# 18-de-77.net
KiCad netlist of a schematic drawn in EAGLE
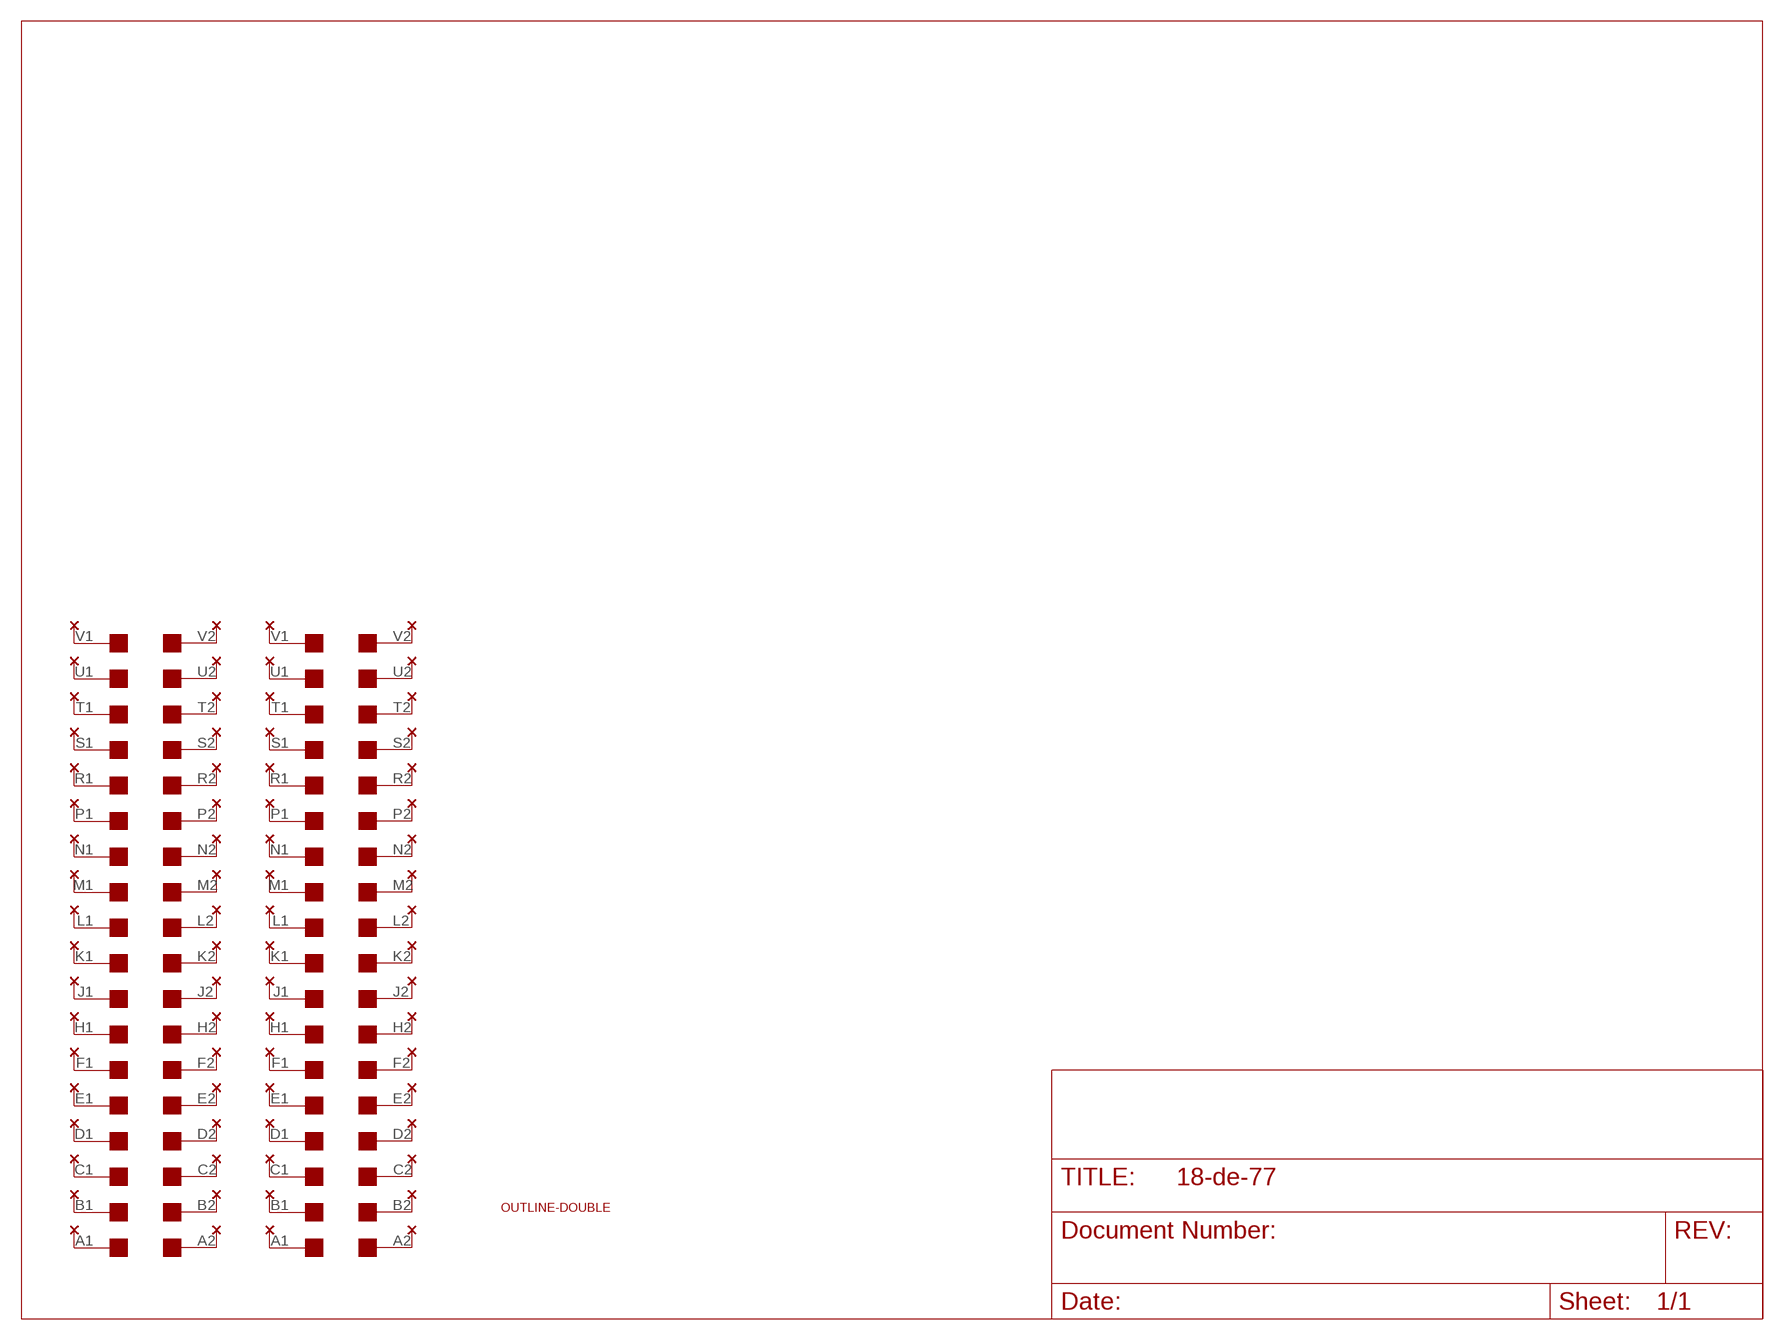
[diagram p0: schematic, sheet 1]

(export (version "E")
  (design (tool "Eeschema 10.0.6"))
  (components
    (comp (ref "U$1")
      (value "SINGLE")
      (footprint "eagle-import:EDGE-CON2")
      (libsource (lib "eagle-import") (part "SINGLE"))
    )
    (comp (ref "U$2")
      (value "THRU-HOLE2A")
      (footprint "eagle-import:THRU-HOLEA")
      (libsource (lib "eagle-import") (part "THRU-HOLE2A"))
    )
    (comp (ref "U$3")
      (value "THRU-HOLE2A")
      (footprint "eagle-import:THRU-HOLEA")
      (libsource (lib "eagle-import") (part "THRU-HOLE2A"))
    )
    (comp (ref "U$4")
      (value "OUTLINE-DOUBLE")
      (footprint "eagle-import:DOUBLE")
      (libsource (lib "eagle-import") (part "OUTLINE-DOUBLE"))
    )
    (comp (ref "U$6")
      (value "SINGLE")
      (footprint "eagle-import:EDGE-CON2")
      (libsource (lib "eagle-import") (part "SINGLE"))
    )
  )
  (nets
    (net (code "1") (name "Net-(U$1A-1)") (class "Default")
      (node (ref "U$1") (pin "A1") (pinfunction "1_A1") (pintype "bidirectional"))
      (node (ref "U$2") (pin "A1") (pinfunction "P$1_A1") (pintype "passive"))
    )
    (net (code "2") (name "Net-(U$1AA-1)") (class "Default")
      (node (ref "U$1") (pin "R1") (pinfunction "1_R1") (pintype "bidirectional"))
      (node (ref "U$2") (pin "R1") (pinfunction "P$1_R1") (pintype "passive"))
    )
    (net (code "3") (name "Net-(U$1AB-1)") (class "Default")
      (node (ref "U$1") (pin "R2") (pinfunction "1_R2") (pintype "bidirectional"))
      (node (ref "U$2") (pin "R2") (pinfunction "P$1_R2") (pintype "passive"))
    )
    (net (code "4") (name "Net-(U$1AC-1)") (class "Default")
      (node (ref "U$1") (pin "S1") (pinfunction "1_S1") (pintype "bidirectional"))
      (node (ref "U$2") (pin "S1") (pinfunction "P$1_S1") (pintype "passive"))
    )
    (net (code "5") (name "Net-(U$1AD-1)") (class "Default")
      (node (ref "U$1") (pin "S2") (pinfunction "1_S2") (pintype "bidirectional"))
      (node (ref "U$2") (pin "S2") (pinfunction "P$1_S2") (pintype "passive"))
    )
    (net (code "6") (name "Net-(U$1AE-1)") (class "Default")
      (node (ref "U$1") (pin "T1") (pinfunction "1_T1") (pintype "bidirectional"))
      (node (ref "U$2") (pin "T1") (pinfunction "P$1_T1") (pintype "passive"))
    )
    (net (code "7") (name "Net-(U$1AF-1)") (class "Default")
      (node (ref "U$1") (pin "T2") (pinfunction "1_T2") (pintype "bidirectional"))
      (node (ref "U$2") (pin "T2") (pinfunction "P$1_T2") (pintype "passive"))
    )
    (net (code "8") (name "Net-(U$1AG-1)") (class "Default")
      (node (ref "U$1") (pin "U1") (pinfunction "1_U1") (pintype "bidirectional"))
      (node (ref "U$2") (pin "U1") (pinfunction "P$1_U1") (pintype "passive"))
    )
    (net (code "9") (name "Net-(U$1AH-1)") (class "Default")
      (node (ref "U$1") (pin "U2") (pinfunction "1_U2") (pintype "bidirectional"))
      (node (ref "U$2") (pin "U2") (pinfunction "P$1_U2") (pintype "passive"))
    )
    (net (code "10") (name "Net-(U$1AI-1)") (class "Default")
      (node (ref "U$1") (pin "V1") (pinfunction "1_V1") (pintype "bidirectional"))
      (node (ref "U$2") (pin "V1") (pinfunction "P$1_V1") (pintype "passive"))
    )
    (net (code "11") (name "Net-(U$1AJ-1)") (class "Default")
      (node (ref "U$1") (pin "V2") (pinfunction "1_V2") (pintype "bidirectional"))
      (node (ref "U$2") (pin "V2") (pinfunction "P$1_V2") (pintype "passive"))
    )
    (net (code "12") (name "Net-(U$1B-1)") (class "Default")
      (node (ref "U$1") (pin "A2") (pinfunction "1_A2") (pintype "bidirectional"))
      (node (ref "U$2") (pin "A2") (pinfunction "P$1_A2") (pintype "passive"))
    )
    (net (code "13") (name "Net-(U$1C-1)") (class "Default")
      (node (ref "U$1") (pin "B1") (pinfunction "1_B1") (pintype "bidirectional"))
      (node (ref "U$2") (pin "B1") (pinfunction "P$1_B1") (pintype "passive"))
    )
    (net (code "14") (name "Net-(U$1D-1)") (class "Default")
      (node (ref "U$1") (pin "B2") (pinfunction "1_B2") (pintype "bidirectional"))
      (node (ref "U$2") (pin "B2") (pinfunction "P$1_B2") (pintype "passive"))
    )
    (net (code "15") (name "Net-(U$1E-1)") (class "Default")
      (node (ref "U$1") (pin "C1") (pinfunction "1_C1") (pintype "bidirectional"))
      (node (ref "U$2") (pin "C1") (pinfunction "P$1_C1") (pintype "passive"))
    )
    (net (code "16") (name "Net-(U$1F-1)") (class "Default")
      (node (ref "U$1") (pin "C2") (pinfunction "1_C2") (pintype "bidirectional"))
      (node (ref "U$2") (pin "C2") (pinfunction "P$1_C2") (pintype "passive"))
    )
    (net (code "17") (name "Net-(U$1G-1)") (class "Default")
      (node (ref "U$1") (pin "D1") (pinfunction "1_D1") (pintype "bidirectional"))
      (node (ref "U$2") (pin "D1") (pinfunction "P$1_D1") (pintype "passive"))
    )
    (net (code "18") (name "Net-(U$1H-1)") (class "Default")
      (node (ref "U$1") (pin "D2") (pinfunction "1_D2") (pintype "bidirectional"))
      (node (ref "U$2") (pin "D2") (pinfunction "P$1_D2") (pintype "passive"))
    )
    (net (code "19") (name "Net-(U$1I-1)") (class "Default")
      (node (ref "U$1") (pin "E1") (pinfunction "1_E1") (pintype "bidirectional"))
      (node (ref "U$2") (pin "E1") (pinfunction "P$1_E1") (pintype "passive"))
    )
    (net (code "20") (name "Net-(U$1J-1)") (class "Default")
      (node (ref "U$1") (pin "E2") (pinfunction "1_E2") (pintype "bidirectional"))
      (node (ref "U$2") (pin "E2") (pinfunction "P$1_E2") (pintype "passive"))
    )
    (net (code "21") (name "Net-(U$1K-1)") (class "Default")
      (node (ref "U$1") (pin "F1") (pinfunction "1_F1") (pintype "bidirectional"))
      (node (ref "U$2") (pin "F1") (pinfunction "P$1_F1") (pintype "passive"))
    )
    (net (code "22") (name "Net-(U$1L-1)") (class "Default")
      (node (ref "U$1") (pin "F2") (pinfunction "1_F2") (pintype "bidirectional"))
      (node (ref "U$2") (pin "F2") (pinfunction "P$1_F2") (pintype "passive"))
    )
    (net (code "23") (name "Net-(U$1M-1)") (class "Default")
      (node (ref "U$1") (pin "H1") (pinfunction "1_H1") (pintype "bidirectional"))
      (node (ref "U$2") (pin "H1") (pinfunction "P$1_H1") (pintype "passive"))
    )
    (net (code "24") (name "Net-(U$1N-1)") (class "Default")
      (node (ref "U$1") (pin "H2") (pinfunction "1_H2") (pintype "bidirectional"))
      (node (ref "U$2") (pin "H2") (pinfunction "P$1_H2") (pintype "passive"))
    )
    (net (code "25") (name "Net-(U$1O-1)") (class "Default")
      (node (ref "U$1") (pin "J1") (pinfunction "1_J1") (pintype "bidirectional"))
      (node (ref "U$2") (pin "J1") (pinfunction "P$1_J1") (pintype "passive"))
    )
    (net (code "26") (name "Net-(U$1P-1)") (class "Default")
      (node (ref "U$1") (pin "J2") (pinfunction "1_J2") (pintype "bidirectional"))
      (node (ref "U$2") (pin "J2") (pinfunction "P$1_J2") (pintype "passive"))
    )
    (net (code "27") (name "Net-(U$1Q-1)") (class "Default")
      (node (ref "U$1") (pin "K1") (pinfunction "1_K1") (pintype "bidirectional"))
      (node (ref "U$2") (pin "K1") (pinfunction "P$1_K1") (pintype "passive"))
    )
    (net (code "28") (name "Net-(U$1R-1)") (class "Default")
      (node (ref "U$1") (pin "K2") (pinfunction "1_K2") (pintype "bidirectional"))
      (node (ref "U$2") (pin "K2") (pinfunction "P$1_K2") (pintype "passive"))
    )
    (net (code "29") (name "Net-(U$1S-1)") (class "Default")
      (node (ref "U$1") (pin "L1") (pinfunction "1_L1") (pintype "bidirectional"))
      (node (ref "U$2") (pin "L1") (pinfunction "P$1_L1") (pintype "passive"))
    )
    (net (code "30") (name "Net-(U$1T-1)") (class "Default")
      (node (ref "U$1") (pin "L2") (pinfunction "1_L2") (pintype "bidirectional"))
      (node (ref "U$2") (pin "L2") (pinfunction "P$1_L2") (pintype "passive"))
    )
    (net (code "31") (name "Net-(U$1U-1)") (class "Default")
      (node (ref "U$1") (pin "M1") (pinfunction "1_M1") (pintype "bidirectional"))
      (node (ref "U$2") (pin "M1") (pinfunction "P$1_M1") (pintype "passive"))
    )
    (net (code "32") (name "Net-(U$1V-1)") (class "Default")
      (node (ref "U$1") (pin "M2") (pinfunction "1_M2") (pintype "bidirectional"))
      (node (ref "U$2") (pin "M2") (pinfunction "P$1_M2") (pintype "passive"))
    )
    (net (code "33") (name "Net-(U$1W-1)") (class "Default")
      (node (ref "U$1") (pin "N1") (pinfunction "1_N1") (pintype "bidirectional"))
      (node (ref "U$2") (pin "N1") (pinfunction "P$1_N1") (pintype "passive"))
    )
    (net (code "34") (name "Net-(U$1X-1)") (class "Default")
      (node (ref "U$1") (pin "N2") (pinfunction "1_N2") (pintype "bidirectional"))
      (node (ref "U$2") (pin "N2") (pinfunction "P$1_N2") (pintype "passive"))
    )
    (net (code "35") (name "Net-(U$1Y-1)") (class "Default")
      (node (ref "U$1") (pin "P1") (pinfunction "1_P1") (pintype "bidirectional"))
      (node (ref "U$2") (pin "P1") (pinfunction "P$1_P1") (pintype "passive"))
    )
    (net (code "36") (name "Net-(U$1Z-1)") (class "Default")
      (node (ref "U$1") (pin "P2") (pinfunction "1_P2") (pintype "bidirectional"))
      (node (ref "U$2") (pin "P2") (pinfunction "P$1_P2") (pintype "passive"))
    )
    (net (code "37") (name "Net-(U$3A-P$1)") (class "Default")
      (node (ref "U$3") (pin "A1") (pinfunction "P$1_A1") (pintype "passive"))
      (node (ref "U$6") (pin "A1") (pinfunction "1_A1") (pintype "bidirectional"))
    )
    (net (code "38") (name "Net-(U$3AA-P$1)") (class "Default")
      (node (ref "U$3") (pin "R1") (pinfunction "P$1_R1") (pintype "passive"))
      (node (ref "U$6") (pin "R1") (pinfunction "1_R1") (pintype "bidirectional"))
    )
    (net (code "39") (name "Net-(U$3AB-P$1)") (class "Default")
      (node (ref "U$3") (pin "R2") (pinfunction "P$1_R2") (pintype "passive"))
      (node (ref "U$6") (pin "R2") (pinfunction "1_R2") (pintype "bidirectional"))
    )
    (net (code "40") (name "Net-(U$3AC-P$1)") (class "Default")
      (node (ref "U$3") (pin "S1") (pinfunction "P$1_S1") (pintype "passive"))
      (node (ref "U$6") (pin "S1") (pinfunction "1_S1") (pintype "bidirectional"))
    )
    (net (code "41") (name "Net-(U$3AD-P$1)") (class "Default")
      (node (ref "U$3") (pin "S2") (pinfunction "P$1_S2") (pintype "passive"))
      (node (ref "U$6") (pin "S2") (pinfunction "1_S2") (pintype "bidirectional"))
    )
    (net (code "42") (name "Net-(U$3AE-P$1)") (class "Default")
      (node (ref "U$3") (pin "T1") (pinfunction "P$1_T1") (pintype "passive"))
      (node (ref "U$6") (pin "T1") (pinfunction "1_T1") (pintype "bidirectional"))
    )
    (net (code "43") (name "Net-(U$3AF-P$1)") (class "Default")
      (node (ref "U$3") (pin "T2") (pinfunction "P$1_T2") (pintype "passive"))
      (node (ref "U$6") (pin "T2") (pinfunction "1_T2") (pintype "bidirectional"))
    )
    (net (code "44") (name "Net-(U$3AG-P$1)") (class "Default")
      (node (ref "U$3") (pin "U1") (pinfunction "P$1_U1") (pintype "passive"))
      (node (ref "U$6") (pin "U1") (pinfunction "1_U1") (pintype "bidirectional"))
    )
    (net (code "45") (name "Net-(U$3AH-P$1)") (class "Default")
      (node (ref "U$3") (pin "U2") (pinfunction "P$1_U2") (pintype "passive"))
      (node (ref "U$6") (pin "U2") (pinfunction "1_U2") (pintype "bidirectional"))
    )
    (net (code "46") (name "Net-(U$3AI-P$1)") (class "Default")
      (node (ref "U$3") (pin "V1") (pinfunction "P$1_V1") (pintype "passive"))
      (node (ref "U$6") (pin "V1") (pinfunction "1_V1") (pintype "bidirectional"))
    )
    (net (code "47") (name "Net-(U$3AJ-P$1)") (class "Default")
      (node (ref "U$3") (pin "V2") (pinfunction "P$1_V2") (pintype "passive"))
      (node (ref "U$6") (pin "V2") (pinfunction "1_V2") (pintype "bidirectional"))
    )
    (net (code "48") (name "Net-(U$3B-P$1)") (class "Default")
      (node (ref "U$3") (pin "A2") (pinfunction "P$1_A2") (pintype "passive"))
      (node (ref "U$6") (pin "A2") (pinfunction "1_A2") (pintype "bidirectional"))
    )
    (net (code "49") (name "Net-(U$3C-P$1)") (class "Default")
      (node (ref "U$3") (pin "B1") (pinfunction "P$1_B1") (pintype "passive"))
      (node (ref "U$6") (pin "B1") (pinfunction "1_B1") (pintype "bidirectional"))
    )
    (net (code "50") (name "Net-(U$3D-P$1)") (class "Default")
      (node (ref "U$3") (pin "B2") (pinfunction "P$1_B2") (pintype "passive"))
      (node (ref "U$6") (pin "B2") (pinfunction "1_B2") (pintype "bidirectional"))
    )
    (net (code "51") (name "Net-(U$3E-P$1)") (class "Default")
      (node (ref "U$3") (pin "C1") (pinfunction "P$1_C1") (pintype "passive"))
      (node (ref "U$6") (pin "C1") (pinfunction "1_C1") (pintype "bidirectional"))
    )
    (net (code "52") (name "Net-(U$3F-P$1)") (class "Default")
      (node (ref "U$3") (pin "C2") (pinfunction "P$1_C2") (pintype "passive"))
      (node (ref "U$6") (pin "C2") (pinfunction "1_C2") (pintype "bidirectional"))
    )
    (net (code "53") (name "Net-(U$3G-P$1)") (class "Default")
      (node (ref "U$3") (pin "D1") (pinfunction "P$1_D1") (pintype "passive"))
      (node (ref "U$6") (pin "D1") (pinfunction "1_D1") (pintype "bidirectional"))
    )
    (net (code "54") (name "Net-(U$3H-P$1)") (class "Default")
      (node (ref "U$3") (pin "D2") (pinfunction "P$1_D2") (pintype "passive"))
      (node (ref "U$6") (pin "D2") (pinfunction "1_D2") (pintype "bidirectional"))
    )
    (net (code "55") (name "Net-(U$3I-P$1)") (class "Default")
      (node (ref "U$3") (pin "E1") (pinfunction "P$1_E1") (pintype "passive"))
      (node (ref "U$6") (pin "E1") (pinfunction "1_E1") (pintype "bidirectional"))
    )
    (net (code "56") (name "Net-(U$3J-P$1)") (class "Default")
      (node (ref "U$3") (pin "E2") (pinfunction "P$1_E2") (pintype "passive"))
      (node (ref "U$6") (pin "E2") (pinfunction "1_E2") (pintype "bidirectional"))
    )
    (net (code "57") (name "Net-(U$3K-P$1)") (class "Default")
      (node (ref "U$3") (pin "F1") (pinfunction "P$1_F1") (pintype "passive"))
      (node (ref "U$6") (pin "F1") (pinfunction "1_F1") (pintype "bidirectional"))
    )
    (net (code "58") (name "Net-(U$3L-P$1)") (class "Default")
      (node (ref "U$3") (pin "F2") (pinfunction "P$1_F2") (pintype "passive"))
      (node (ref "U$6") (pin "F2") (pinfunction "1_F2") (pintype "bidirectional"))
    )
    (net (code "59") (name "Net-(U$3M-P$1)") (class "Default")
      (node (ref "U$3") (pin "H1") (pinfunction "P$1_H1") (pintype "passive"))
      (node (ref "U$6") (pin "H1") (pinfunction "1_H1") (pintype "bidirectional"))
    )
    (net (code "60") (name "Net-(U$3N-P$1)") (class "Default")
      (node (ref "U$3") (pin "H2") (pinfunction "P$1_H2") (pintype "passive"))
      (node (ref "U$6") (pin "H2") (pinfunction "1_H2") (pintype "bidirectional"))
    )
    (net (code "61") (name "Net-(U$3O-P$1)") (class "Default")
      (node (ref "U$3") (pin "J1") (pinfunction "P$1_J1") (pintype "passive"))
      (node (ref "U$6") (pin "J1") (pinfunction "1_J1") (pintype "bidirectional"))
    )
    (net (code "62") (name "Net-(U$3P-P$1)") (class "Default")
      (node (ref "U$3") (pin "J2") (pinfunction "P$1_J2") (pintype "passive"))
      (node (ref "U$6") (pin "J2") (pinfunction "1_J2") (pintype "bidirectional"))
    )
    (net (code "63") (name "Net-(U$3Q-P$1)") (class "Default")
      (node (ref "U$3") (pin "K1") (pinfunction "P$1_K1") (pintype "passive"))
      (node (ref "U$6") (pin "K1") (pinfunction "1_K1") (pintype "bidirectional"))
    )
    (net (code "64") (name "Net-(U$3R-P$1)") (class "Default")
      (node (ref "U$3") (pin "K2") (pinfunction "P$1_K2") (pintype "passive"))
      (node (ref "U$6") (pin "K2") (pinfunction "1_K2") (pintype "bidirectional"))
    )
    (net (code "65") (name "Net-(U$3S-P$1)") (class "Default")
      (node (ref "U$3") (pin "L1") (pinfunction "P$1_L1") (pintype "passive"))
      (node (ref "U$6") (pin "L1") (pinfunction "1_L1") (pintype "bidirectional"))
    )
    (net (code "66") (name "Net-(U$3T-P$1)") (class "Default")
      (node (ref "U$3") (pin "L2") (pinfunction "P$1_L2") (pintype "passive"))
      (node (ref "U$6") (pin "L2") (pinfunction "1_L2") (pintype "bidirectional"))
    )
    (net (code "67") (name "Net-(U$3U-P$1)") (class "Default")
      (node (ref "U$3") (pin "M1") (pinfunction "P$1_M1") (pintype "passive"))
      (node (ref "U$6") (pin "M1") (pinfunction "1_M1") (pintype "bidirectional"))
    )
    (net (code "68") (name "Net-(U$3V-P$1)") (class "Default")
      (node (ref "U$3") (pin "M2") (pinfunction "P$1_M2") (pintype "passive"))
      (node (ref "U$6") (pin "M2") (pinfunction "1_M2") (pintype "bidirectional"))
    )
    (net (code "69") (name "Net-(U$3W-P$1)") (class "Default")
      (node (ref "U$3") (pin "N1") (pinfunction "P$1_N1") (pintype "passive"))
      (node (ref "U$6") (pin "N1") (pinfunction "1_N1") (pintype "bidirectional"))
    )
    (net (code "70") (name "Net-(U$3X-P$1)") (class "Default")
      (node (ref "U$3") (pin "N2") (pinfunction "P$1_N2") (pintype "passive"))
      (node (ref "U$6") (pin "N2") (pinfunction "1_N2") (pintype "bidirectional"))
    )
    (net (code "71") (name "Net-(U$3Y-P$1)") (class "Default")
      (node (ref "U$3") (pin "P1") (pinfunction "P$1_P1") (pintype "passive"))
      (node (ref "U$6") (pin "P1") (pinfunction "1_P1") (pintype "bidirectional"))
    )
    (net (code "72") (name "Net-(U$3Z-P$1)") (class "Default")
      (node (ref "U$3") (pin "P2") (pinfunction "P$1_P2") (pintype "passive"))
      (node (ref "U$6") (pin "P2") (pinfunction "1_P2") (pintype "bidirectional"))
    )
  )
)
